# pwr.net
KiCad netlist of a schematic drawn in EAGLE
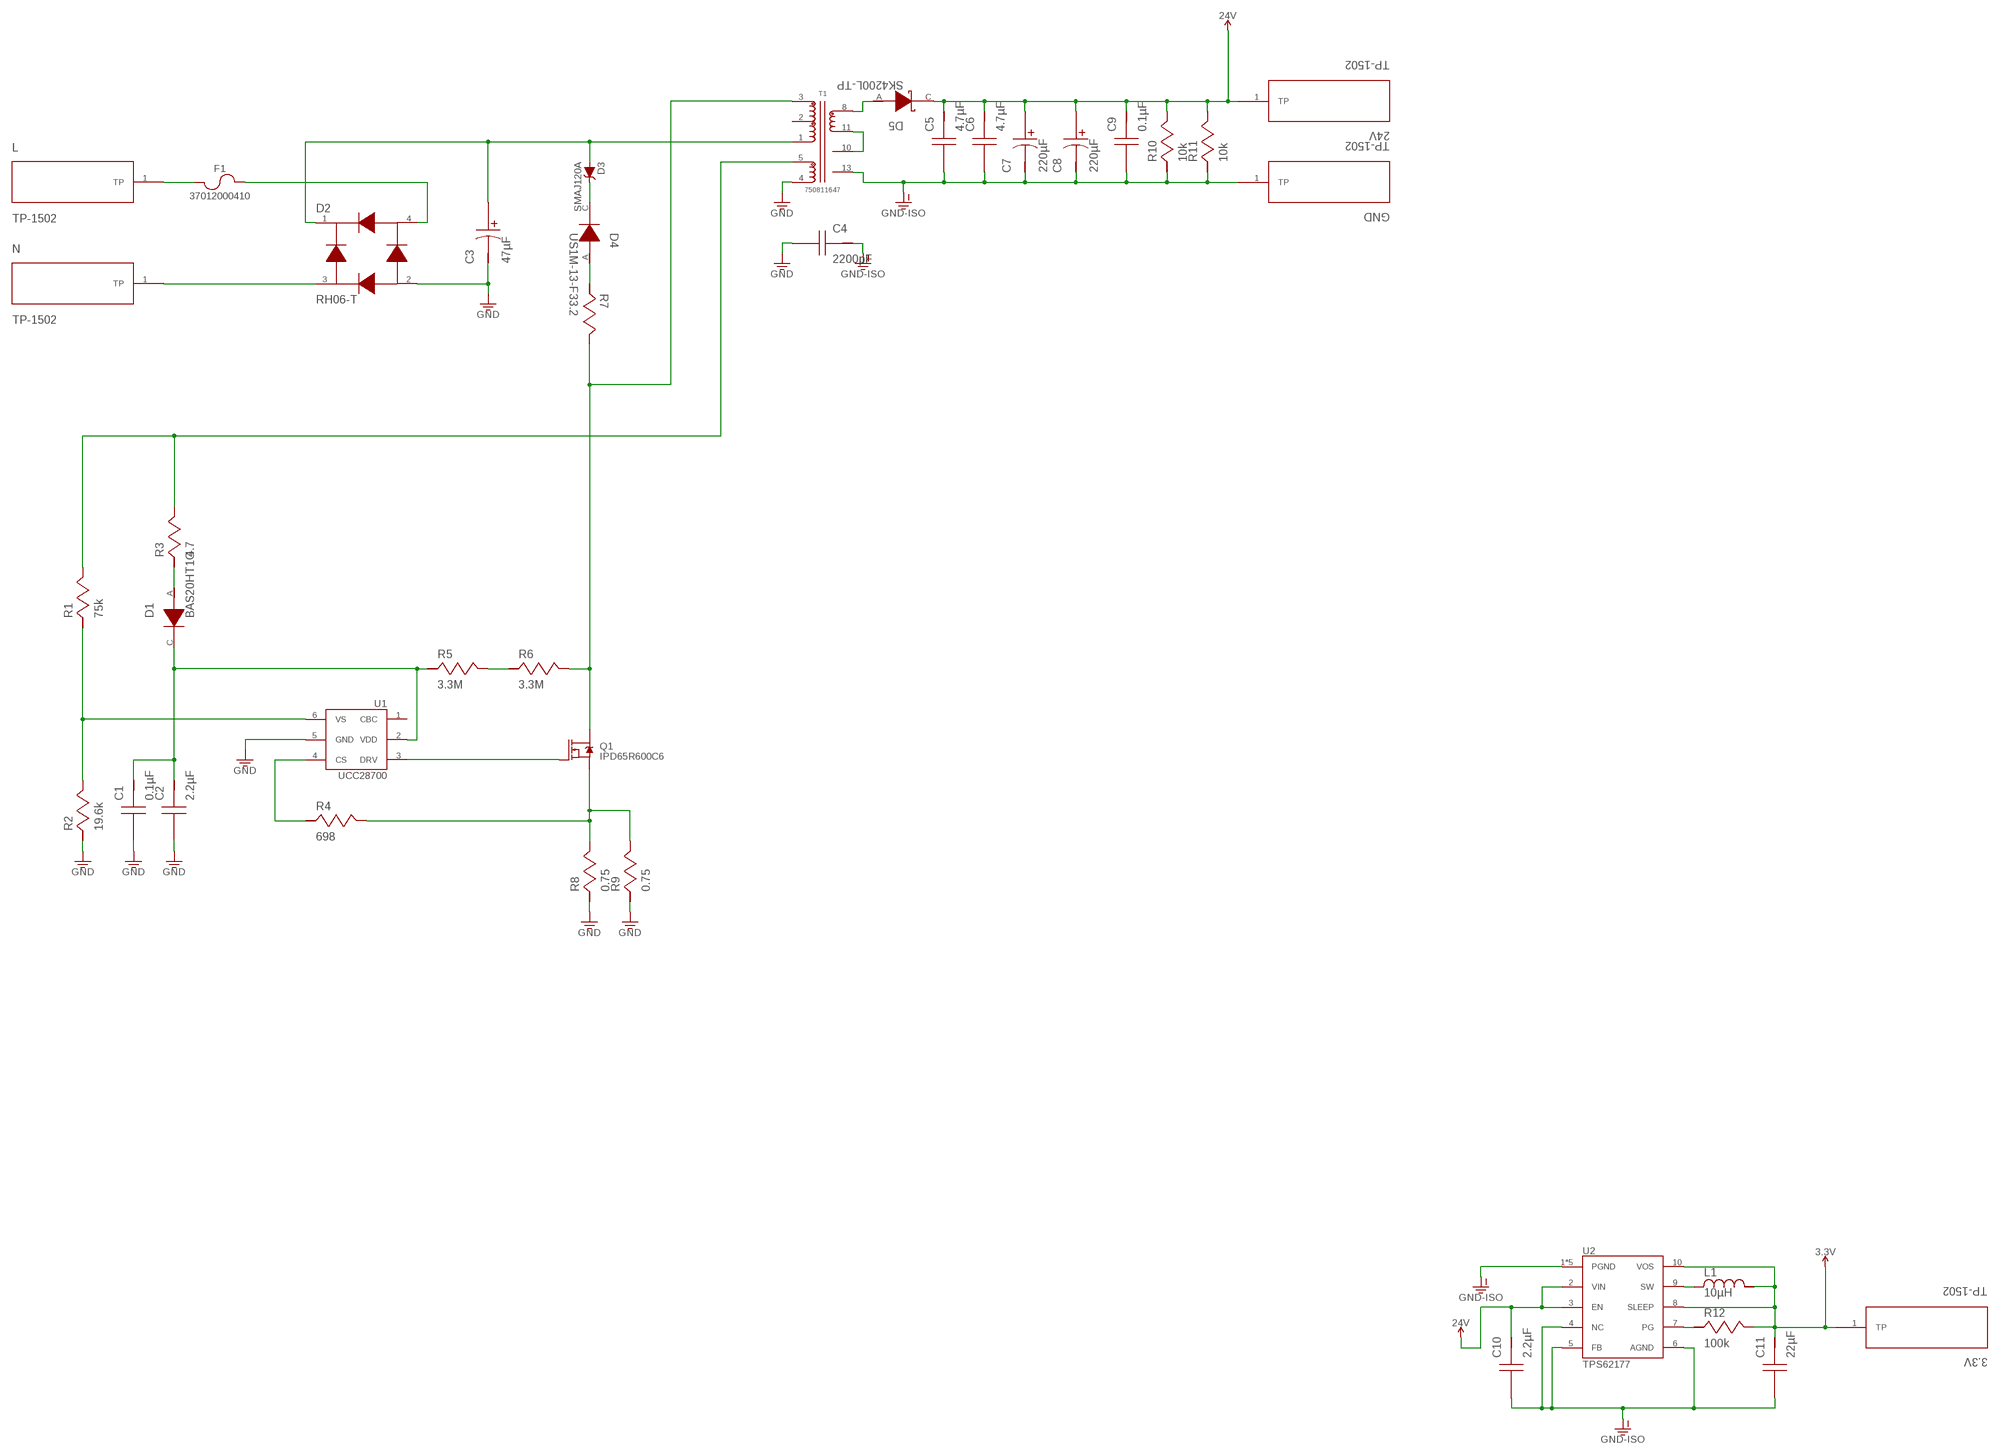
[diagram p0: schematic, sheet 1]

(export (version "E")
  (design (tool "Eeschema 10.0.6"))
  (components
    (comp (ref "3.3V")
      (value "TP-1502")
      (footprint "eagle-import:TP-1502")
      (libsource (lib "eagle-import") (part "TP-1502"))
    )
    (comp (ref "24V")
      (value "TP-1502")
      (footprint "eagle-import:TP-1502")
      (libsource (lib "eagle-import") (part "TP-1502"))
    )
    (comp (ref "C1")
      (value "0.1µF")
      (footprint "eagle-import:0603")
      (fields
        (field (name "DIGIKEY_PART_NUMBER") "478-5052-1-ND")
        (field (name "MANUFACTURER") "AVX Corporation")
        (field (name "PART_NUMBER") "06035C104KAT2A")
      )
      (libsource (lib "eagle-import") (part "06035C104KAT2A"))
    )
    (comp (ref "C2")
      (value "2.2µF")
      (footprint "eagle-import:1206")
      (fields
        (field (name "DIGIKEY_PART_NUMBER") "490-6514-1-ND")
        (field (name "MANUFACTURER") "Murata Electronics North America")
        (field (name "PART_NUMBER") "GRM31CR61H225KA88L")
      )
      (libsource (lib "eagle-import") (part "GRM31CR61H225KA88L"))
    )
    (comp (ref "C3")
      (value "47µF")
      (footprint "eagle-import:CAPPR7.5-18X20")
      (fields
        (field (name "DIGIKEY_PART_NUMBER") "P13546-ND")
        (field (name "MANUFACTURER") "Panasonic Electronic Components")
        (field (name "PART_NUMBER") "EEU-ED2G470S")
      )
      (libsource (lib "eagle-import") (part "EEU-ED2G470S"))
    )
    (comp (ref "C4")
      (value "2200pF")
      (footprint "eagle-import:DE1E3KX222MA4BL01")
      (fields
        (field (name "DIGIKEY_PART_NUMBER") "490-9384-ND")
        (field (name "MANUFACTURER") "Murata Electronics North America")
        (field (name "PART_NUMBER") "DE1E3KX222MA4BN01F")
      )
      (libsource (lib "eagle-import") (part "DE1E3KX222MA4BN01F"))
    )
    (comp (ref "C5")
      (value "4.7µF")
      (footprint "eagle-import:1206")
      (fields
        (field (name "DIGIKEY_PART_NUMBER") "587-2994-1-ND")
        (field (name "MANUFACTURER") "Taiyo Yuden")
        (field (name "PART_NUMBER") "UMK316AB7475KL-T")
      )
      (libsource (lib "eagle-import") (part "UMK316AB7475KL-T"))
    )
    (comp (ref "C6")
      (value "4.7µF")
      (footprint "eagle-import:1206")
      (fields
        (field (name "DIGIKEY_PART_NUMBER") "587-2994-1-ND")
        (field (name "MANUFACTURER") "Taiyo Yuden")
        (field (name "PART_NUMBER") "UMK316AB7475KL-T")
      )
      (libsource (lib "eagle-import") (part "UMK316AB7475KL-T"))
    )
    (comp (ref "C7")
      (value "220µF")
      (footprint "eagle-import:CAPPR5-10X16")
      (fields
        (field (name "DIGIKEY_PART_NUMBER") "493-14552-1-ND")
        (field (name "MANUFACTURER") "Nichicon")
        (field (name "PART_NUMBER") "UHE1V221MPD6")
      )
      (libsource (lib "eagle-import") (part "UHE1V221MPD6"))
    )
    (comp (ref "C8")
      (value "220µF")
      (footprint "eagle-import:CAPPR5-10X16")
      (fields
        (field (name "DIGIKEY_PART_NUMBER") "493-14552-1-ND")
        (field (name "MANUFACTURER") "Nichicon")
        (field (name "PART_NUMBER") "UHE1V221MPD6")
      )
      (libsource (lib "eagle-import") (part "UHE1V221MPD6"))
    )
    (comp (ref "C9")
      (value "0.1µF")
      (footprint "eagle-import:0805")
      (fields
        (field (name "DIGIKEY_PART_NUMBER") "478-3755-1-ND")
        (field (name "MANUFACTURER") "AVX Corporation")
        (field (name "PART_NUMBER") "08053C104KAT2A")
      )
      (libsource (lib "eagle-import") (part "08053C104KAT2A"))
    )
    (comp (ref "C10")
      (value "2.2µF")
      (footprint "eagle-import:0603")
      (fields
        (field (name "DIGIKEY_PART_NUMBER") "445-8025-1-ND")
        (field (name "MANUFACTURER") "TDK Corporation")
        (field (name "PART_NUMBER") "C1608X5R1V225K080AC")
      )
      (libsource (lib "eagle-import") (part "C1608X5R1V225K080AC"))
    )
    (comp (ref "C11")
      (value "22µF")
      (footprint "eagle-import:0805")
      (fields
        (field (name "DIGIKEY_PART_NUMBER") "490-1719-1-ND")
        (field (name "MANUFACTURER") "Murata Electronics North America")
        (field (name "PART_NUMBER") "GRM21BR60J226ME39L")
      )
      (libsource (lib "eagle-import") (part "GRM21BR60J226ME39L"))
    )
    (comp (ref "D1")
      (value "BAS20HT1G")
      (footprint "eagle-import:SOD-323")
      (fields
        (field (name "DIGIKEY_PART_NUMBER") "BAS20HT1GOSCT-ND")
        (field (name "MANUFACTURER") "ON Semiconductor")
      )
      (libsource (lib "eagle-import") (part "BAS20HT1G"))
    )
    (comp (ref "D2")
      (value "RH06-T")
      (footprint "eagle-import:MINIDIP")
      (fields
        (field (name "DIGIKEY_PART_NUMBER") "RH06DICT-ND")
        (field (name "MANUFACTURER") "Diodes Incorporated")
      )
      (libsource (lib "eagle-import") (part "RH06-T"))
    )
    (comp (ref "D3")
      (value "SMAJ120A")
      (footprint "eagle-import:SMA")
      (fields
        (field (name "DIGIKEY_PART_NUMBER") "SMAJ120ALFCT-ND")
        (field (name "MANUFACTURER") "Littelfuse Inc.")
      )
      (libsource (lib "eagle-import") (part "SMAJ120A"))
    )
    (comp (ref "D4")
      (value "US1M-13-F")
      (footprint "eagle-import:SMA")
      (fields
        (field (name "DIGIKEY_PART_NUMBER") "US1M-FDICT-ND")
        (field (name "MANUFACTURER") "Diodes Incorporated")
      )
      (libsource (lib "eagle-import") (part "US1M-13-F"))
    )
    (comp (ref "D5")
      (value "SK4200L-TP")
      (footprint "eagle-import:SMC")
      (fields
        (field (name "DIGIKEY_PART_NUMBER") "SK4200L-TPMSCT-ND")
        (field (name "MANUFACTURER") "Micro Commercial Co")
      )
      (libsource (lib "eagle-import") (part "SK4200L-TP"))
    )
    (comp (ref "F1")
      (value "37012000410")
      (footprint "eagle-import:TR5_FUSE_8.5")
      (fields
        (field (name "DIGIKEY_PART_NUMBER") "WK4957BK-ND")
        (field (name "MANUFACTURER") "Littelfuse Inc.")
      )
      (libsource (lib "eagle-import") (part "37012000410"))
    )
    (comp (ref "GND")
      (value "TP-1502")
      (footprint "eagle-import:TP-1502")
      (libsource (lib "eagle-import") (part "TP-1502"))
    )
    (comp (ref "L")
      (value "TP-1502")
      (footprint "eagle-import:TP-1502")
      (libsource (lib "eagle-import") (part "TP-1502"))
    )
    (comp (ref "L1")
      (value "10µH")
      (footprint "eagle-import:SDR0503")
      (fields
        (field (name "DIGIKEY_PART_NUMBER") "SDR0503-100MLCT-ND")
        (field (name "MANUFACTURER") "Bourns Inc.")
        (field (name "PART_NUMBER") "SDR0503-100ML")
      )
      (libsource (lib "eagle-import") (part "SDR0503-100ML"))
    )
    (comp (ref "N")
      (value "TP-1502")
      (footprint "eagle-import:TP-1502")
      (libsource (lib "eagle-import") (part "TP-1502"))
    )
    (comp (ref "Q1")
      (value "IPD65R600C6")
      (footprint "eagle-import:TO-252")
      (fields
        (field (name "DIGIKEY_PART_NUMBER") "IPD65R600C6BTMA1CT-ND")
        (field (name "MANUFACTURER") "Infineon Technologies")
      )
      (libsource (lib "eagle-import") (part "IPD65R600C6"))
    )
    (comp (ref "R1")
      (value "75k")
      (footprint "eagle-import:0603")
      (fields
        (field (name "DIGIKEY_PART_NUMBER") "541-75.0KHCT-ND")
        (field (name "MANUFACTURER") "Vishay Dale")
        (field (name "PART_NUMBER") "CRCW060375K0FKEA")
      )
      (libsource (lib "eagle-import") (part "CRCW060375K0FKEA"))
    )
    (comp (ref "R2")
      (value "19.6k")
      (footprint "eagle-import:0603")
      (fields
        (field (name "DIGIKEY_PART_NUMBER") "541-19.6KHCT-ND")
        (field (name "MANUFACTURER") "Vishay Dale")
        (field (name "PART_NUMBER") "CRCW060319K6FKEA")
      )
      (libsource (lib "eagle-import") (part "CRCW060319K6FKEA"))
    )
    (comp (ref "R3")
      (value "4.7")
      (footprint "eagle-import:1206")
      (fields
        (field (name "DIGIKEY_PART_NUMBER") "541-4.7ECT-ND")
        (field (name "MANUFACTURER") "Vishay Dale")
        (field (name "PART_NUMBER") "CRCW12064R70JNEA")
      )
      (libsource (lib "eagle-import") (part "CRCW12064R70JNEA"))
    )
    (comp (ref "R4")
      (value "698")
      (footprint "eagle-import:1206")
      (fields
        (field (name "DIGIKEY_PART_NUMBER") "541-698FCT-ND")
        (field (name "MANUFACTURER") "Vishay Dale")
        (field (name "PART_NUMBER") "CRCW1206698RFKEA")
      )
      (libsource (lib "eagle-import") (part "CRCW1206698RFKEA"))
    )
    (comp (ref "R5")
      (value "3.3M")
      (footprint "eagle-import:0805")
      (fields
        (field (name "DIGIKEY_PART_NUMBER") "541-3.3MACT-ND")
        (field (name "MANUFACTURER") "Vishay Dale")
        (field (name "PART_NUMBER") "CRCW08053M30JNEA")
      )
      (libsource (lib "eagle-import") (part "CRCW08053M30JNEA"))
    )
    (comp (ref "R6")
      (value "3.3M")
      (footprint "eagle-import:0805")
      (fields
        (field (name "DIGIKEY_PART_NUMBER") "541-3.3MACT-ND")
        (field (name "MANUFACTURER") "Vishay Dale")
        (field (name "PART_NUMBER") "CRCW08053M30JNEA")
      )
      (libsource (lib "eagle-import") (part "CRCW08053M30JNEA"))
    )
    (comp (ref "R7")
      (value "33.2")
      (footprint "eagle-import:1210")
      (fields
        (field (name "DIGIKEY_PART_NUMBER") "541-33.2AACT-ND")
        (field (name "MANUFACTURER") "Vishay Dale")
        (field (name "PART_NUMBER") "CRCW121033R2FKEA")
      )
      (libsource (lib "eagle-import") (part "CRCW121033R2FKEA"))
    )
    (comp (ref "R8")
      (value "0.75")
      (footprint "eagle-import:1206")
      (fields
        (field (name "DIGIKEY_PART_NUMBER") "CSR1206FKR750CT-ND")
        (field (name "MANUFACTURER") "Stackpole Electronics Inc.")
        (field (name "PART_NUMBER") "CSR1206FKR750")
      )
      (libsource (lib "eagle-import") (part "CSR1206FKR750"))
    )
    (comp (ref "R9")
      (value "0.75")
      (footprint "eagle-import:1206")
      (fields
        (field (name "DIGIKEY_PART_NUMBER") "CSR1206FKR750CT-ND")
        (field (name "MANUFACTURER") "Stackpole Electronics Inc.")
        (field (name "PART_NUMBER") "CSR1206FKR750")
      )
      (libsource (lib "eagle-import") (part "CSR1206FKR750"))
    )
    (comp (ref "R10")
      (value "10k")
      (footprint "eagle-import:1206")
      (fields
        (field (name "DIGIKEY_PART_NUMBER") "541-10KECT-ND")
        (field (name "MANUFACTURER") "Vishay Dale")
        (field (name "PART_NUMBER") "CRCW120610K0JNEA")
      )
      (libsource (lib "eagle-import") (part "CRCW120610K0JNEA"))
    )
    (comp (ref "R11")
      (value "10k")
      (footprint "eagle-import:1206")
      (fields
        (field (name "DIGIKEY_PART_NUMBER") "541-10KECT-ND")
        (field (name "MANUFACTURER") "Vishay Dale")
        (field (name "PART_NUMBER") "CRCW120610K0JNEA")
      )
      (libsource (lib "eagle-import") (part "CRCW120610K0JNEA"))
    )
    (comp (ref "R12")
      (value "100k")
      (footprint "eagle-import:0402")
      (fields
        (field (name "DIGIKEY_PART_NUMBER") "541-100KLCT-ND")
        (field (name "MANUFACTURER") "Vishay Dale")
        (field (name "PART_NUMBER") "CRCW0402100KFKED")
      )
      (libsource (lib "eagle-import") (part "CRCW0402100KFKED"))
    )
    (comp (ref "T1")
      (value "750811647")
      (footprint "eagle-import:750811647")
      (fields (field (name "MANUFACTURER") "Wurth Electronics Midcom"))
      (libsource (lib "eagle-import") (part "750811647"))
    )
    (comp (ref "U1")
      (value "UCC28700")
      (footprint "eagle-import:SOT-23(6)")
      (fields
        (field (name "DIGIKEY_PART_NUMBER") "296-39536-1-ND")
        (field (name "MANUFACTURER") "Texas Instruments")
        (field (name "PART_NUMBER") "UCC28700DBVR")
      )
      (libsource (lib "eagle-import") (part "UCC28700"))
    )
    (comp (ref "U2")
      (value "TPS62177")
      (footprint "eagle-import:P-WSON(10)")
      (fields
        (field (name "DIGIKEY_PART_NUMBER") "296-41856-1-ND")
        (field (name "MANUFACTURER") "Texas Instruments")
        (field (name "PART_NUMBER") "TPS62177DQCR")
      )
      (libsource (lib "eagle-import") (part "TPS62177"))
    )
  )
  (nets
    (net (code "1") (name "3.3V") (class "Default")
      (node (ref "3.3V") (pin "1") (pinfunction "TP_1") (pintype "passive"))
      (node (ref "C11") (pin "1") (pinfunction "1_1") (pintype "passive"))
      (node (ref "L1") (pin "2") (pinfunction "2_2") (pintype "passive"))
      (node (ref "R12") (pin "1") (pinfunction "1_1") (pintype "passive"))
      (node (ref "U2") (pin "10") (pinfunction "VOS_10") (pintype "bidirectional"))
      (node (ref "U2") (pin "8") (pinfunction "SLEEP_8") (pintype "bidirectional"))
    )
    (net (code "2") (name "24V") (class "Default")
      (node (ref "24V") (pin "1") (pinfunction "TP_1") (pintype "passive"))
      (node (ref "C10") (pin "1") (pinfunction "1_1") (pintype "passive"))
      (node (ref "C5") (pin "1") (pinfunction "1_1") (pintype "passive"))
      (node (ref "C6") (pin "1") (pinfunction "1_1") (pintype "passive"))
      (node (ref "C7") (pin "P$1") (pinfunction "1_P$1") (pintype "passive"))
      (node (ref "C8") (pin "P$1") (pinfunction "1_P$1") (pintype "passive"))
      (node (ref "C9") (pin "1") (pinfunction "1_1") (pintype "passive"))
      (node (ref "D5") (pin "C") (pinfunction "C_C") (pintype "passive"))
      (node (ref "R10") (pin "1") (pinfunction "1_1") (pintype "passive"))
      (node (ref "R11") (pin "1") (pinfunction "1_1") (pintype "passive"))
      (node (ref "U2") (pin "2") (pinfunction "VIN_2") (pintype "bidirectional"))
      (node (ref "U2") (pin "3") (pinfunction "EN_3") (pintype "bidirectional"))
    )
    (net (code "3") (name "GND") (class "Default")
      (node (ref "C1") (pin "2") (pinfunction "2_2") (pintype "passive"))
      (node (ref "C2") (pin "2") (pinfunction "2_2") (pintype "passive"))
      (node (ref "C3") (pin "P$2") (pinfunction "2_P$2") (pintype "passive"))
      (node (ref "C4") (pin "2") (pinfunction "2_2") (pintype "passive"))
      (node (ref "D2") (pin "2") (pinfunction "P$2_2") (pintype "bidirectional"))
      (node (ref "R2") (pin "2") (pinfunction "2_2") (pintype "passive"))
      (node (ref "R8") (pin "2") (pinfunction "2_2") (pintype "passive"))
      (node (ref "R9") (pin "2") (pinfunction "2_2") (pintype "passive"))
      (node (ref "T1") (pin "4") (pinfunction "4_4") (pintype "bidirectional"))
      (node (ref "U1") (pin "5") (pinfunction "GND_5") (pintype "bidirectional"))
    )
    (net (code "4") (name "GND-ISO") (class "Default")
      (node (ref "C10") (pin "2") (pinfunction "2_2") (pintype "passive"))
      (node (ref "C11") (pin "2") (pinfunction "2_2") (pintype "passive"))
      (node (ref "C4") (pin "1") (pinfunction "1_1") (pintype "passive"))
      (node (ref "C5") (pin "2") (pinfunction "2_2") (pintype "passive"))
      (node (ref "C6") (pin "2") (pinfunction "2_2") (pintype "passive"))
      (node (ref "C7") (pin "P$2") (pinfunction "2_P$2") (pintype "passive"))
      (node (ref "C8") (pin "P$2") (pinfunction "2_P$2") (pintype "passive"))
      (node (ref "C9") (pin "2") (pinfunction "2_2") (pintype "passive"))
      (node (ref "GND") (pin "1") (pinfunction "TP_1") (pintype "passive"))
      (node (ref "R10") (pin "2") (pinfunction "2_2") (pintype "passive"))
      (node (ref "R11") (pin "2") (pinfunction "2_2") (pintype "passive"))
      (node (ref "T1") (pin "13") (pinfunction "13_13") (pintype "bidirectional"))
      (node (ref "U2") (pin "1") (pinfunction "PGND_1") (pintype "bidirectional"))
      (node (ref "U2") (pin "4") (pinfunction "NC_4") (pintype "bidirectional"))
      (node (ref "U2") (pin "5") (pinfunction "FB_5") (pintype "bidirectional"))
      (node (ref "U2") (pin "6") (pinfunction "AGND_6") (pintype "bidirectional"))
      (node (ref "U2") (pin "GND") (pinfunction "PGND_GND") (pintype "bidirectional"))
      (node (ref "U2") (pin "P$1") (pinfunction "PGND_P$1") (pintype "bidirectional"))
      (node (ref "U2") (pin "P$10") (pinfunction "PGND_P$10") (pintype "bidirectional"))
      (node (ref "U2") (pin "P$2") (pinfunction "PGND_P$2") (pintype "bidirectional"))
    )
    (net (code "5") (name "Net-(C3-1)") (class "Default")
      (node (ref "C3") (pin "P$1") (pinfunction "1_P$1") (pintype "passive"))
      (node (ref "D2") (pin "1") (pinfunction "P$1_1") (pintype "bidirectional"))
      (node (ref "D3") (pin "A") (pinfunction "A_A") (pintype "passive"))
      (node (ref "T1") (pin "1") (pinfunction "1_1") (pintype "bidirectional"))
    )
    (net (code "6") (name "Net-(D1-PadA)") (class "Default")
      (node (ref "D1") (pin "A") (pinfunction "A_A") (pintype "passive"))
      (node (ref "R3") (pin "2") (pinfunction "2_2") (pintype "passive"))
    )
    (net (code "7") (name "Net-(D2-P$3)") (class "Default")
      (node (ref "D2") (pin "3") (pinfunction "P$3_3") (pintype "bidirectional"))
      (node (ref "N") (pin "1") (pinfunction "TP_1") (pintype "passive"))
    )
    (net (code "8") (name "Net-(D2-P$4)") (class "Default")
      (node (ref "D2") (pin "4") (pinfunction "P$4_4") (pintype "bidirectional"))
      (node (ref "F1") (pin "2") (pinfunction "2_2") (pintype "bidirectional"))
    )
    (net (code "9") (name "Net-(D3-PadC)") (class "Default")
      (node (ref "D3") (pin "C") (pinfunction "C_C") (pintype "passive"))
      (node (ref "D4") (pin "C") (pinfunction "C_C") (pintype "passive"))
    )
    (net (code "10") (name "Net-(D4-PadA)") (class "Default")
      (node (ref "D4") (pin "A") (pinfunction "A_A") (pintype "passive"))
      (node (ref "R7") (pin "2") (pinfunction "2_2") (pintype "passive"))
    )
    (net (code "11") (name "Net-(D5-PadA)") (class "Default")
      (node (ref "D5") (pin "A") (pinfunction "A_A") (pintype "passive"))
      (node (ref "T1") (pin "8") (pinfunction "8_8") (pintype "bidirectional"))
    )
    (net (code "12") (name "Net-(L-TP)") (class "Default")
      (node (ref "F1") (pin "1") (pinfunction "1_1") (pintype "bidirectional"))
      (node (ref "L") (pin "1") (pinfunction "TP_1") (pintype "passive"))
    )
    (net (code "13") (name "Net-(Q1-D)") (class "Default")
      (node (ref "Q1") (pin "2") (pinfunction "D_2") (pintype "bidirectional"))
      (node (ref "R6") (pin "1") (pinfunction "1_1") (pintype "passive"))
      (node (ref "R7") (pin "1") (pinfunction "1_1") (pintype "passive"))
      (node (ref "T1") (pin "3") (pinfunction "3_3") (pintype "bidirectional"))
    )
    (net (code "14") (name "Net-(Q1-G)") (class "Default")
      (node (ref "Q1") (pin "1") (pinfunction "G_1") (pintype "bidirectional"))
      (node (ref "U1") (pin "3") (pinfunction "DRV_3") (pintype "bidirectional"))
    )
    (net (code "15") (name "Net-(Q1-S)") (class "Default")
      (node (ref "Q1") (pin "3") (pinfunction "S_3") (pintype "bidirectional"))
      (node (ref "R4") (pin "1") (pinfunction "1_1") (pintype "passive"))
      (node (ref "R8") (pin "1") (pinfunction "1_1") (pintype "passive"))
      (node (ref "R9") (pin "1") (pinfunction "1_1") (pintype "passive"))
    )
    (net (code "16") (name "Net-(R1-Pad1)") (class "Default")
      (node (ref "R1") (pin "1") (pinfunction "1_1") (pintype "passive"))
      (node (ref "R3") (pin "1") (pinfunction "1_1") (pintype "passive"))
      (node (ref "T1") (pin "5") (pinfunction "5_5") (pintype "bidirectional"))
    )
    (net (code "17") (name "Net-(R5-Pad1)") (class "Default")
      (node (ref "R5") (pin "1") (pinfunction "1_1") (pintype "passive"))
      (node (ref "R6") (pin "2") (pinfunction "2_2") (pintype "passive"))
    )
    (net (code "18") (name "Net-(T1-Pad10)") (class "Default")
      (node (ref "T1") (pin "10") (pinfunction "10_10") (pintype "bidirectional"))
      (node (ref "T1") (pin "11") (pinfunction "11_11") (pintype "bidirectional"))
    )
    (net (code "19") (name "Net-(U1-CS)") (class "Default")
      (node (ref "R4") (pin "2") (pinfunction "2_2") (pintype "passive"))
      (node (ref "U1") (pin "4") (pinfunction "CS_4") (pintype "bidirectional"))
    )
    (net (code "20") (name "Net-(U1-VDD)") (class "Default")
      (node (ref "C1") (pin "1") (pinfunction "1_1") (pintype "passive"))
      (node (ref "C2") (pin "1") (pinfunction "1_1") (pintype "passive"))
      (node (ref "D1") (pin "C") (pinfunction "C_C") (pintype "passive"))
      (node (ref "R5") (pin "2") (pinfunction "2_2") (pintype "passive"))
      (node (ref "U1") (pin "2") (pinfunction "VDD_2") (pintype "bidirectional"))
    )
    (net (code "21") (name "Net-(U1-VS)") (class "Default")
      (node (ref "R1") (pin "2") (pinfunction "2_2") (pintype "passive"))
      (node (ref "R2") (pin "1") (pinfunction "1_1") (pintype "passive"))
      (node (ref "U1") (pin "6") (pinfunction "VS_6") (pintype "bidirectional"))
    )
    (net (code "22") (name "Net-(U2-PG)") (class "Default")
      (node (ref "R12") (pin "2") (pinfunction "2_2") (pintype "passive"))
      (node (ref "U2") (pin "7") (pinfunction "PG_7") (pintype "bidirectional"))
    )
    (net (code "23") (name "Net-(U2-SW)") (class "Default")
      (node (ref "L1") (pin "1") (pinfunction "1_1") (pintype "passive"))
      (node (ref "U2") (pin "9") (pinfunction "SW_9") (pintype "bidirectional"))
    )
    (net (code "24") (name "unconnected-(T1-Pad2)") (class "Default")
      (node (ref "T1") (pin "2") (pinfunction "2_2") (pintype "bidirectional"))
    )
    (net (code "25") (name "unconnected-(U1-CBC-Pad1)") (class "Default")
      (node (ref "U1") (pin "1") (pinfunction "CBC_1") (pintype "bidirectional"))
    )
  )
)
